# board_schematic.net
KiCad netlist of a schematic drawn in EAGLE
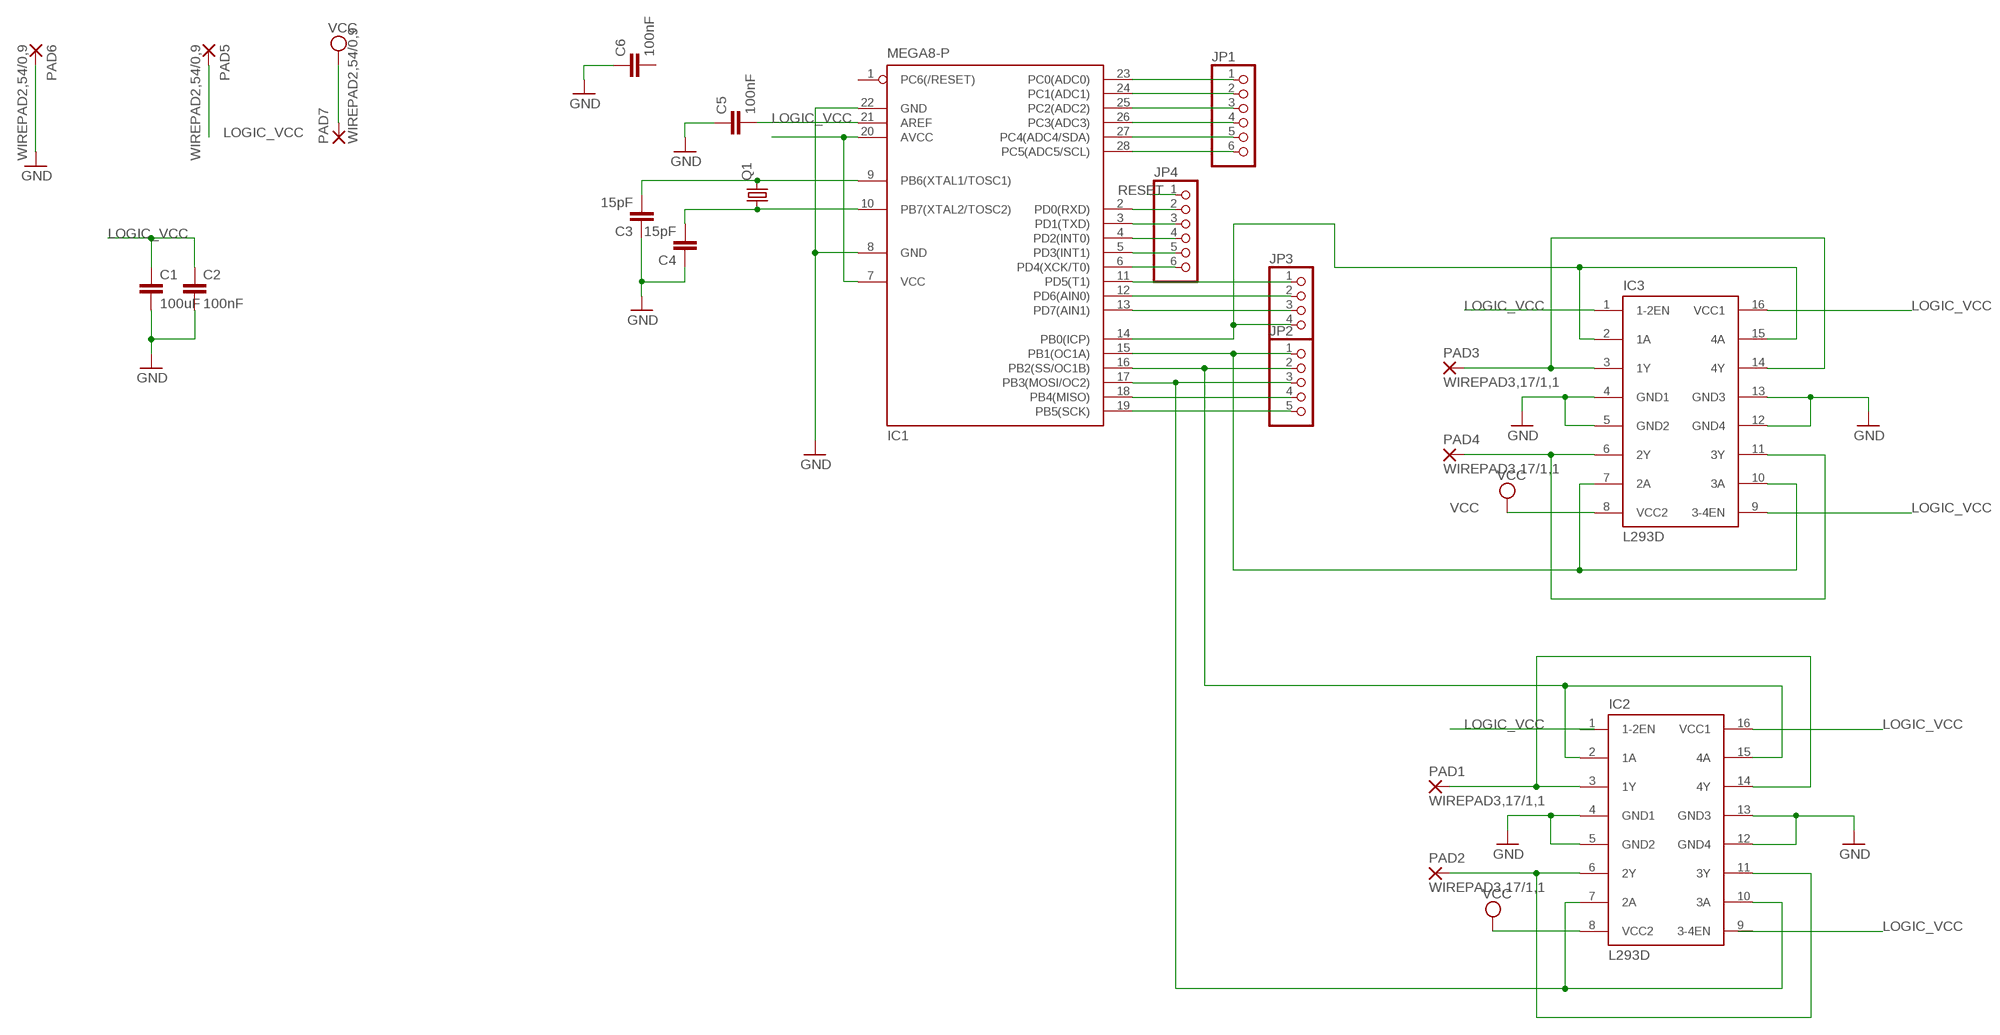
[diagram p0: schematic, sheet 1]

(export (version "E")
  (design (tool "Eeschema 10.0.6"))
  (components
    (comp (ref "C1")
      (value "100uF")
      (footprint "eagle-import:C050-045X075")
      (libsource (lib "eagle-import") (part "C-EU050-045X075"))
    )
    (comp (ref "C2")
      (value "100nF")
      (footprint "eagle-import:C050-045X075")
      (libsource (lib "eagle-import") (part "C-EU050-045X075"))
    )
    (comp (ref "C3")
      (value "15pF")
      (footprint "eagle-import:C5B2.5")
      (libsource (lib "eagle-import") (part "C5/2.5"))
    )
    (comp (ref "C4")
      (value "15pF")
      (footprint "eagle-import:C5B2.5")
      (libsource (lib "eagle-import") (part "C5/2.5"))
    )
    (comp (ref "C5")
      (value "100nF")
      (footprint "eagle-import:C050-045X075")
      (libsource (lib "eagle-import") (part "C-EU050-045X075"))
    )
    (comp (ref "C6")
      (value "100nF")
      (footprint "eagle-import:C050-045X075")
      (libsource (lib "eagle-import") (part "C-EU050-045X075"))
    )
    (comp (ref "IC1")
      (value "MEGA8-P")
      (footprint "eagle-import:DIL28-3")
      (libsource (lib "eagle-import") (part "MEGA8-P"))
    )
    (comp (ref "IC2")
      (value "L293D")
      (footprint "eagle-import:DIL16")
      (libsource (lib "eagle-import") (part "L293D"))
    )
    (comp (ref "IC3")
      (value "L293D")
      (footprint "eagle-import:DIL16")
      (libsource (lib "eagle-import") (part "L293D"))
    )
    (comp (ref "JP1")
      (value "PINHD-1X6")
      (footprint "eagle-import:1X06")
      (libsource (lib "eagle-import") (part "PINHD-1X6"))
    )
    (comp (ref "JP2")
      (value "PINHD-1X5")
      (footprint "eagle-import:1X05")
      (libsource (lib "eagle-import") (part "PINHD-1X5"))
    )
    (comp (ref "JP3")
      (value "PINHD-1X4")
      (footprint "eagle-import:1X04")
      (libsource (lib "eagle-import") (part "PINHD-1X4"))
    )
    (comp (ref "JP4")
      (value "PINHD-1X6")
      (footprint "eagle-import:1X06")
      (libsource (lib "eagle-import") (part "PINHD-1X6"))
    )
    (comp (ref "PAD1")
      (value "WIREPAD3,17/1,1")
      (footprint "eagle-import:3,17_1,1")
      (libsource (lib "eagle-import") (part "WIREPAD3,17/1,1"))
    )
    (comp (ref "PAD2")
      (value "WIREPAD3,17/1,1")
      (footprint "eagle-import:3,17_1,1")
      (libsource (lib "eagle-import") (part "WIREPAD3,17/1,1"))
    )
    (comp (ref "PAD3")
      (value "WIREPAD3,17/1,1")
      (footprint "eagle-import:3,17_1,1")
      (libsource (lib "eagle-import") (part "WIREPAD3,17/1,1"))
    )
    (comp (ref "PAD4")
      (value "WIREPAD3,17/1,1")
      (footprint "eagle-import:3,17_1,1")
      (libsource (lib "eagle-import") (part "WIREPAD3,17/1,1"))
    )
    (comp (ref "PAD5")
      (value "WIREPAD2,54/0,9")
      (footprint "eagle-import:2,54_0,9")
      (libsource (lib "eagle-import") (part "WIREPAD2,54/0,9"))
    )
    (comp (ref "PAD6")
      (value "WIREPAD2,54/0,9")
      (footprint "eagle-import:2,54_0,9")
      (libsource (lib "eagle-import") (part "WIREPAD2,54/0,9"))
    )
    (comp (ref "PAD7")
      (value "WIREPAD2,54/0,9")
      (footprint "eagle-import:2,54_0,9")
      (libsource (lib "eagle-import") (part "WIREPAD2,54/0,9"))
    )
    (comp (ref "Q1")
      (value "CRYSTALHC49S")
      (footprint "eagle-import:HC49_S")
      (libsource (lib "eagle-import") (part "CRYSTALHC49S"))
    )
  )
  (nets
    (net (code "1") (name "/LOGIC_VCC") (class "Default")
      (node (ref "C1") (pin "1") (pinfunction "1_1") (pintype "passive"))
      (node (ref "C2") (pin "1") (pinfunction "1_1") (pintype "passive"))
      (node (ref "IC1") (pin "20") (pinfunction "AVCC_20") (pintype "power_in"))
      (node (ref "IC1") (pin "7") (pinfunction "VCC_7") (pintype "power_in"))
      (node (ref "IC2") (pin "16") (pinfunction "VCC1_16") (pintype "power_in"))
      (node (ref "IC3") (pin "1") (pinfunction "1-2EN_1") (pintype "input"))
      (node (ref "IC3") (pin "16") (pinfunction "VCC1_16") (pintype "power_in"))
      (node (ref "IC3") (pin "9") (pinfunction "3-4EN_9") (pintype "input"))
      (node (ref "PAD5") (pin "1") (pinfunction "P_1") (pintype "passive"))
    )
    (net (code "2") (name "/RESET") (class "Default")
      (node (ref "JP4") (pin "1") (pinfunction "1_1") (pintype "passive"))
    )
    (net (code "3") (name "GND") (class "Default")
      (node (ref "C1") (pin "2") (pinfunction "2_2") (pintype "passive"))
      (node (ref "C2") (pin "2") (pinfunction "2_2") (pintype "passive"))
      (node (ref "C3") (pin "1") (pinfunction "1_1") (pintype "passive"))
      (node (ref "C4") (pin "1") (pinfunction "1_1") (pintype "passive"))
      (node (ref "C5") (pin "1") (pinfunction "1_1") (pintype "passive"))
      (node (ref "C6") (pin "1") (pinfunction "1_1") (pintype "passive"))
      (node (ref "IC1") (pin "22") (pinfunction "GND_22") (pintype "power_in"))
      (node (ref "IC1") (pin "8") (pinfunction "GND_8") (pintype "power_in"))
      (node (ref "IC2") (pin "12") (pinfunction "GND4_12") (pintype "power_in"))
      (node (ref "IC2") (pin "13") (pinfunction "GND3_13") (pintype "power_in"))
      (node (ref "IC2") (pin "4") (pinfunction "GND1_4") (pintype "power_in"))
      (node (ref "IC2") (pin "5") (pinfunction "GND2_5") (pintype "power_in"))
      (node (ref "IC3") (pin "12") (pinfunction "GND4_12") (pintype "power_in"))
      (node (ref "IC3") (pin "13") (pinfunction "GND3_13") (pintype "power_in"))
      (node (ref "IC3") (pin "4") (pinfunction "GND1_4") (pintype "power_in"))
      (node (ref "IC3") (pin "5") (pinfunction "GND2_5") (pintype "power_in"))
      (node (ref "PAD6") (pin "1") (pinfunction "P_1") (pintype "passive"))
    )
    (net (code "4") (name "Net-(IC1-AREF)") (class "Default")
      (node (ref "C5") (pin "2") (pinfunction "2_2") (pintype "passive"))
      (node (ref "IC1") (pin "21") (pinfunction "AREF_21") (pintype "passive"))
    )
    (net (code "5") (name "Net-(IC1-PB0(ICP))") (class "Default")
      (node (ref "IC1") (pin "14") (pinfunction "PB0(ICP)_14") (pintype "bidirectional"))
      (node (ref "IC3") (pin "15") (pinfunction "4A_15") (pintype "input"))
      (node (ref "IC3") (pin "2") (pinfunction "1A_2") (pintype "input"))
      (node (ref "JP3") (pin "4") (pinfunction "4_4") (pintype "passive"))
    )
    (net (code "6") (name "Net-(IC1-PB1(OC1A))") (class "Default")
      (node (ref "IC1") (pin "15") (pinfunction "PB1(OC1A)_15") (pintype "bidirectional"))
      (node (ref "IC3") (pin "10") (pinfunction "3A_10") (pintype "input"))
      (node (ref "IC3") (pin "7") (pinfunction "2A_7") (pintype "input"))
      (node (ref "JP2") (pin "1") (pinfunction "1_1") (pintype "passive"))
    )
    (net (code "7") (name "Net-(IC1-PB2(SS{slash}OC1B))") (class "Default")
      (node (ref "IC1") (pin "16") (pinfunction "PB2(SS/OC1B)_16") (pintype "bidirectional"))
      (node (ref "IC2") (pin "15") (pinfunction "4A_15") (pintype "input"))
      (node (ref "IC2") (pin "2") (pinfunction "1A_2") (pintype "input"))
      (node (ref "JP2") (pin "2") (pinfunction "2_2") (pintype "passive"))
    )
    (net (code "8") (name "Net-(IC1-PB3(MOSI{slash}OC2))") (class "Default")
      (node (ref "IC1") (pin "17") (pinfunction "PB3(MOSI/OC2)_17") (pintype "bidirectional"))
      (node (ref "IC2") (pin "10") (pinfunction "3A_10") (pintype "input"))
      (node (ref "IC2") (pin "7") (pinfunction "2A_7") (pintype "input"))
      (node (ref "JP2") (pin "3") (pinfunction "3_3") (pintype "passive"))
    )
    (net (code "9") (name "Net-(IC1-PB4(MISO))") (class "Default")
      (node (ref "IC1") (pin "18") (pinfunction "PB4(MISO)_18") (pintype "bidirectional"))
      (node (ref "JP2") (pin "4") (pinfunction "4_4") (pintype "passive"))
    )
    (net (code "10") (name "Net-(IC1-PB5(SCK))") (class "Default")
      (node (ref "IC1") (pin "19") (pinfunction "PB5(SCK)_19") (pintype "bidirectional"))
      (node (ref "JP2") (pin "5") (pinfunction "5_5") (pintype "passive"))
    )
    (net (code "11") (name "Net-(IC1-PB6(XTAL1{slash}TOSC1))") (class "Default")
      (node (ref "C3") (pin "2") (pinfunction "2_2") (pintype "passive"))
      (node (ref "IC1") (pin "9") (pinfunction "PB6(XTAL1/TOSC1)_9") (pintype "bidirectional"))
      (node (ref "Q1") (pin "2") (pinfunction "2_2") (pintype "passive"))
    )
    (net (code "12") (name "Net-(IC1-PB7(XTAL2{slash}TOSC2))") (class "Default")
      (node (ref "C4") (pin "2") (pinfunction "2_2") (pintype "passive"))
      (node (ref "IC1") (pin "10") (pinfunction "PB7(XTAL2/TOSC2)_10") (pintype "bidirectional"))
      (node (ref "Q1") (pin "1") (pinfunction "1_1") (pintype "passive"))
    )
    (net (code "13") (name "Net-(IC1-PC0(ADC0))") (class "Default")
      (node (ref "IC1") (pin "23") (pinfunction "PC0(ADC0)_23") (pintype "bidirectional"))
      (node (ref "JP1") (pin "1") (pinfunction "1_1") (pintype "passive"))
    )
    (net (code "14") (name "Net-(IC1-PC1(ADC1))") (class "Default")
      (node (ref "IC1") (pin "24") (pinfunction "PC1(ADC1)_24") (pintype "bidirectional"))
      (node (ref "JP1") (pin "2") (pinfunction "2_2") (pintype "passive"))
    )
    (net (code "15") (name "Net-(IC1-PC2(ADC2))") (class "Default")
      (node (ref "IC1") (pin "25") (pinfunction "PC2(ADC2)_25") (pintype "bidirectional"))
      (node (ref "JP1") (pin "3") (pinfunction "3_3") (pintype "passive"))
    )
    (net (code "16") (name "Net-(IC1-PC3(ADC3))") (class "Default")
      (node (ref "IC1") (pin "26") (pinfunction "PC3(ADC3)_26") (pintype "bidirectional"))
      (node (ref "JP1") (pin "4") (pinfunction "4_4") (pintype "passive"))
    )
    (net (code "17") (name "Net-(IC1-PC4(ADC4{slash}SDA))") (class "Default")
      (node (ref "IC1") (pin "27") (pinfunction "PC4(ADC4/SDA)_27") (pintype "bidirectional"))
      (node (ref "JP1") (pin "5") (pinfunction "5_5") (pintype "passive"))
    )
    (net (code "18") (name "Net-(IC1-PC5(ADC5{slash}SCL))") (class "Default")
      (node (ref "IC1") (pin "28") (pinfunction "PC5(ADC5/SCL)_28") (pintype "bidirectional"))
      (node (ref "JP1") (pin "6") (pinfunction "6_6") (pintype "passive"))
    )
    (net (code "19") (name "Net-(IC1-PD0(RXD))") (class "Default")
      (node (ref "IC1") (pin "2") (pinfunction "PD0(RXD)_2") (pintype "bidirectional"))
      (node (ref "JP4") (pin "2") (pinfunction "2_2") (pintype "passive"))
    )
    (net (code "20") (name "Net-(IC1-PD1(TXD))") (class "Default")
      (node (ref "IC1") (pin "3") (pinfunction "PD1(TXD)_3") (pintype "bidirectional"))
      (node (ref "JP4") (pin "3") (pinfunction "3_3") (pintype "passive"))
    )
    (net (code "21") (name "Net-(IC1-PD2(INT0))") (class "Default")
      (node (ref "IC1") (pin "4") (pinfunction "PD2(INT0)_4") (pintype "bidirectional"))
      (node (ref "JP4") (pin "4") (pinfunction "4_4") (pintype "passive"))
    )
    (net (code "22") (name "Net-(IC1-PD3(INT1))") (class "Default")
      (node (ref "IC1") (pin "5") (pinfunction "PD3(INT1)_5") (pintype "bidirectional"))
      (node (ref "JP4") (pin "5") (pinfunction "5_5") (pintype "passive"))
    )
    (net (code "23") (name "Net-(IC1-PD4(XCK{slash}T0))") (class "Default")
      (node (ref "IC1") (pin "6") (pinfunction "PD4(XCK/T0)_6") (pintype "bidirectional"))
      (node (ref "JP4") (pin "6") (pinfunction "6_6") (pintype "passive"))
    )
    (net (code "24") (name "Net-(IC1-PD5(T1))") (class "Default")
      (node (ref "IC1") (pin "11") (pinfunction "PD5(T1)_11") (pintype "bidirectional"))
      (node (ref "JP3") (pin "1") (pinfunction "1_1") (pintype "passive"))
    )
    (net (code "25") (name "Net-(IC1-PD6(AIN0))") (class "Default")
      (node (ref "IC1") (pin "12") (pinfunction "PD6(AIN0)_12") (pintype "bidirectional"))
      (node (ref "JP3") (pin "2") (pinfunction "2_2") (pintype "passive"))
    )
    (net (code "26") (name "Net-(IC1-PD7(AIN1))") (class "Default")
      (node (ref "IC1") (pin "13") (pinfunction "PD7(AIN1)_13") (pintype "bidirectional"))
      (node (ref "JP3") (pin "3") (pinfunction "3_3") (pintype "passive"))
    )
    (net (code "27") (name "Net-(IC2-1Y)") (class "Default")
      (node (ref "IC2") (pin "14") (pinfunction "4Y_14") (pintype "output"))
      (node (ref "IC2") (pin "3") (pinfunction "1Y_3") (pintype "output"))
      (node (ref "PAD1") (pin "1") (pinfunction "P_1") (pintype "passive"))
    )
    (net (code "28") (name "Net-(IC2-2Y)") (class "Default")
      (node (ref "IC2") (pin "11") (pinfunction "3Y_11") (pintype "output"))
      (node (ref "IC2") (pin "6") (pinfunction "2Y_6") (pintype "output"))
      (node (ref "PAD2") (pin "1") (pinfunction "P_1") (pintype "passive"))
    )
    (net (code "29") (name "Net-(IC3-1Y)") (class "Default")
      (node (ref "IC3") (pin "14") (pinfunction "4Y_14") (pintype "output"))
      (node (ref "IC3") (pin "3") (pinfunction "1Y_3") (pintype "output"))
      (node (ref "PAD3") (pin "1") (pinfunction "P_1") (pintype "passive"))
    )
    (net (code "30") (name "Net-(IC3-2Y)") (class "Default")
      (node (ref "IC3") (pin "11") (pinfunction "3Y_11") (pintype "output"))
      (node (ref "IC3") (pin "6") (pinfunction "2Y_6") (pintype "output"))
      (node (ref "PAD4") (pin "1") (pinfunction "P_1") (pintype "passive"))
    )
    (net (code "31") (name "VCC") (class "Default")
      (node (ref "IC2") (pin "8") (pinfunction "VCC2_8") (pintype "power_in"))
      (node (ref "IC3") (pin "8") (pinfunction "VCC2_8") (pintype "power_in"))
      (node (ref "PAD7") (pin "1") (pinfunction "P_1") (pintype "passive"))
    )
    (net (code "32") (name "unconnected-(C6-Pad2)") (class "Default")
      (node (ref "C6") (pin "2") (pinfunction "2_2") (pintype "passive"))
    )
    (net (code "33") (name "unconnected-(IC1-PC6({slash}RESET)-Pad1)") (class "Default")
      (node (ref "IC1") (pin "1") (pinfunction "PC6(/RESET)_1") (pintype "bidirectional"))
    )
    (net (code "34") (name "unconnected-(IC2-1-2EN-Pad1)") (class "Default")
      (node (ref "IC2") (pin "1") (pinfunction "1-2EN_1") (pintype "input"))
    )
    (net (code "35") (name "unconnected-(IC2-3-4EN-Pad9)") (class "Default")
      (node (ref "IC2") (pin "9") (pinfunction "3-4EN_9") (pintype "input"))
    )
  )
)
